# reg.net
KiCad netlist of a schematic drawn in Altium Designer
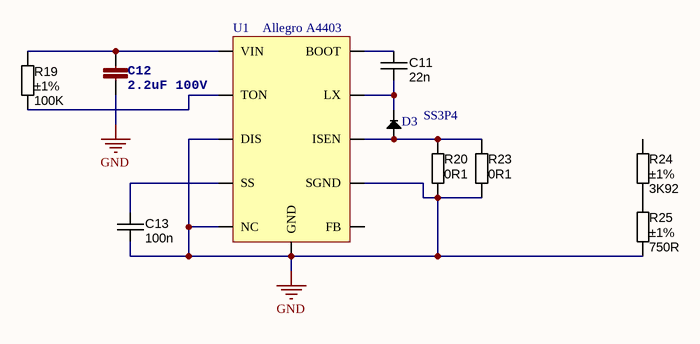
[diagram p0: reg.SchDoc]

(export (version "E")
  (design (tool "Eeschema 10.0.6"))
  (components
    (comp (ref "C11")
      (value "22n")
      (footprint "CAPC1608X90N")
      (description "Capacitor SMD Cer 100nF 10% 50V X7R 0603")
      (fields (field (name "TOLERANCE") "±10%") (field (name "Comment") "approved sub OK"))
      (libsource (lib "PBL - Capacitors") (part "CAPC_100n_0603_X7R_50V_10%"))
    )
    (comp (ref "C12")
      (value "2.2uF 100V")
      (footprint "1210")
      (libsource (lib "SparkFun-Capacitors") (part "10UF50V20%(1210)"))
    )
    (comp (ref "C13")
      (value "100n")
      (footprint "CAPC1608X90N")
      (description "Capacitor SMD Cer 100nF 10% 50V X7R 0603")
      (fields (field (name "TOLERANCE") "±10%") (field (name "Comment") "approved sub OK"))
      (libsource (lib "PBL - Capacitors") (part "CAPC_100n_0603_X7R_50V_10%"))
    )
    (comp (ref "D3") (value "SS3P4") (footprint "SS3P4") (libsource (lib "Schlib1") (part "SS3P4")))
    (comp (ref "R19")
      (value "100K")
      (footprint "RESC2012X70N")
      (description "Resistor SMD chip 4.7k Ohm 0.125W 1% 0805")
      (fields (field (name "TOLERANCE") "±1%") (field (name "Comment") "Thick Film"))
      (libsource (lib "PBL - Resistors") (part "RES_4K7_0805_1%"))
    )
    (comp (ref "R20")
      (value "0R1")
      (footprint "RESC3216X70N")
      (description "Resistor, SMD chip")
      (fields (field (name "Comment") "RES_NL_1206"))
      (libsource (lib "PBL - Resistors") (part "RES_NL_1206"))
    )
    (comp (ref "R23")
      (value "0R1")
      (footprint "RESC3216X70N")
      (description "Resistor, SMD chip")
      (fields (field (name "Comment") "RES_NL_1206"))
      (libsource (lib "PBL - Resistors") (part "RES_NL_1206"))
    )
    (comp (ref "R24")
      (value "3K92")
      (footprint "RESC2012X70N")
      (description "Resistor SMD chip 4.7k Ohm 0.125W 1% 0805")
      (fields (field (name "TOLERANCE") "±1%") (field (name "Comment") "Thick Film"))
      (libsource (lib "PBL - Resistors") (part "RES_4K7_0805_1%"))
    )
    (comp (ref "R25")
      (value "750R")
      (footprint "RESC2012X70N")
      (description "Resistor SMD chip 4.7k Ohm 0.125W 1% 0805")
      (fields (field (name "TOLERANCE") "±1%") (field (name "Comment") "Thick Film"))
      (libsource (lib "PBL - Resistors") (part "RES_4K7_0805_1%"))
    )
    (comp (ref "U1")
      (value "Allegro A4403")
      (libsource (lib "Schlib1") (part "A4403 Allegro Buck Regulator"))
    )
  )
  (nets
    (net (code "1") (name "GND") (class "Default")
      (node (ref "C12") (pin "2") (pinfunction "2_2") (pintype "passive"))
      (node (ref "C13") (pin "2") (pintype "passive"))
      (node (ref "R20") (pin "1") (pinfunction "1_1") (pintype "passive"))
      (node (ref "R23") (pin "1") (pinfunction "1_1") (pintype "passive"))
      (node (ref "R25") (pin "2") (pinfunction "2_2") (pintype "passive"))
      (node (ref "U1") (pin "DIS") (pinfunction "DIS_DIS") (pintype "passive"))
      (node (ref "U1") (pin "GND") (pinfunction "GND_GND") (pintype "passive"))
      (node (ref "U1") (pin "NC") (pinfunction "NC_NC") (pintype "passive"))
      (node (ref "U1") (pin "SGND") (pinfunction "SGND_SGND") (pintype "passive"))
    )
    (net (code "2") (name "Net-(C11-Pad1)") (class "Default")
      (node (ref "C11") (pin "1") (pintype "passive"))
      (node (ref "U1") (pin "BOOT") (pinfunction "BOOT_BOOT") (pintype "passive"))
    )
    (net (code "3") (name "Net-(C11-Pad2)") (class "Default")
      (node (ref "C11") (pin "2") (pintype "passive"))
      (node (ref "D3") (pin "2") (pinfunction "2_2") (pintype "passive"))
      (node (ref "U1") (pin "LX") (pinfunction "LX_LX") (pintype "passive"))
    )
    (net (code "4") (name "Net-(C12-Pad1)") (class "Default")
      (node (ref "C12") (pin "1") (pinfunction "1_1") (pintype "passive"))
      (node (ref "R19") (pin "1") (pinfunction "1_1") (pintype "passive"))
      (node (ref "U1") (pin "VIN") (pinfunction "VIN_VIN") (pintype "passive"))
    )
    (net (code "5") (name "Net-(C13-Pad1)") (class "Default")
      (node (ref "C13") (pin "1") (pintype "passive"))
      (node (ref "U1") (pin "SS") (pinfunction "SS_SS") (pintype "passive"))
    )
    (net (code "6") (name "Net-(D3-Pad1)") (class "Default")
      (node (ref "D3") (pin "1") (pinfunction "1_1") (pintype "passive"))
      (node (ref "R20") (pin "2") (pinfunction "2_2") (pintype "passive"))
      (node (ref "R23") (pin "2") (pinfunction "2_2") (pintype "passive"))
      (node (ref "U1") (pin "ISEN") (pinfunction "ISEN_ISEN") (pintype "passive"))
    )
    (net (code "7") (name "Net-(R19-Pad2)") (class "Default")
      (node (ref "R19") (pin "2") (pinfunction "2_2") (pintype "passive"))
      (node (ref "U1") (pin "TON") (pinfunction "TON_TON") (pintype "passive"))
    )
    (net (code "8") (name "Net-(R24-Pad2)") (class "Default")
      (node (ref "R24") (pin "2") (pinfunction "2_2") (pintype "passive"))
      (node (ref "R25") (pin "1") (pinfunction "1_1") (pintype "passive"))
    )
    (net (code "9") (name "unconnected-(R24-Pad1)") (class "Default")
      (node (ref "R24") (pin "1") (pinfunction "1_1") (pintype "passive"))
    )
    (net (code "10") (name "unconnected-(U1-PadFB)") (class "Default")
      (node (ref "U1") (pin "FB") (pinfunction "FB_FB") (pintype "passive"))
    )
  )
)
